# InstrumentationBoard.net
KiCad netlist of a schematic drawn in EAGLE
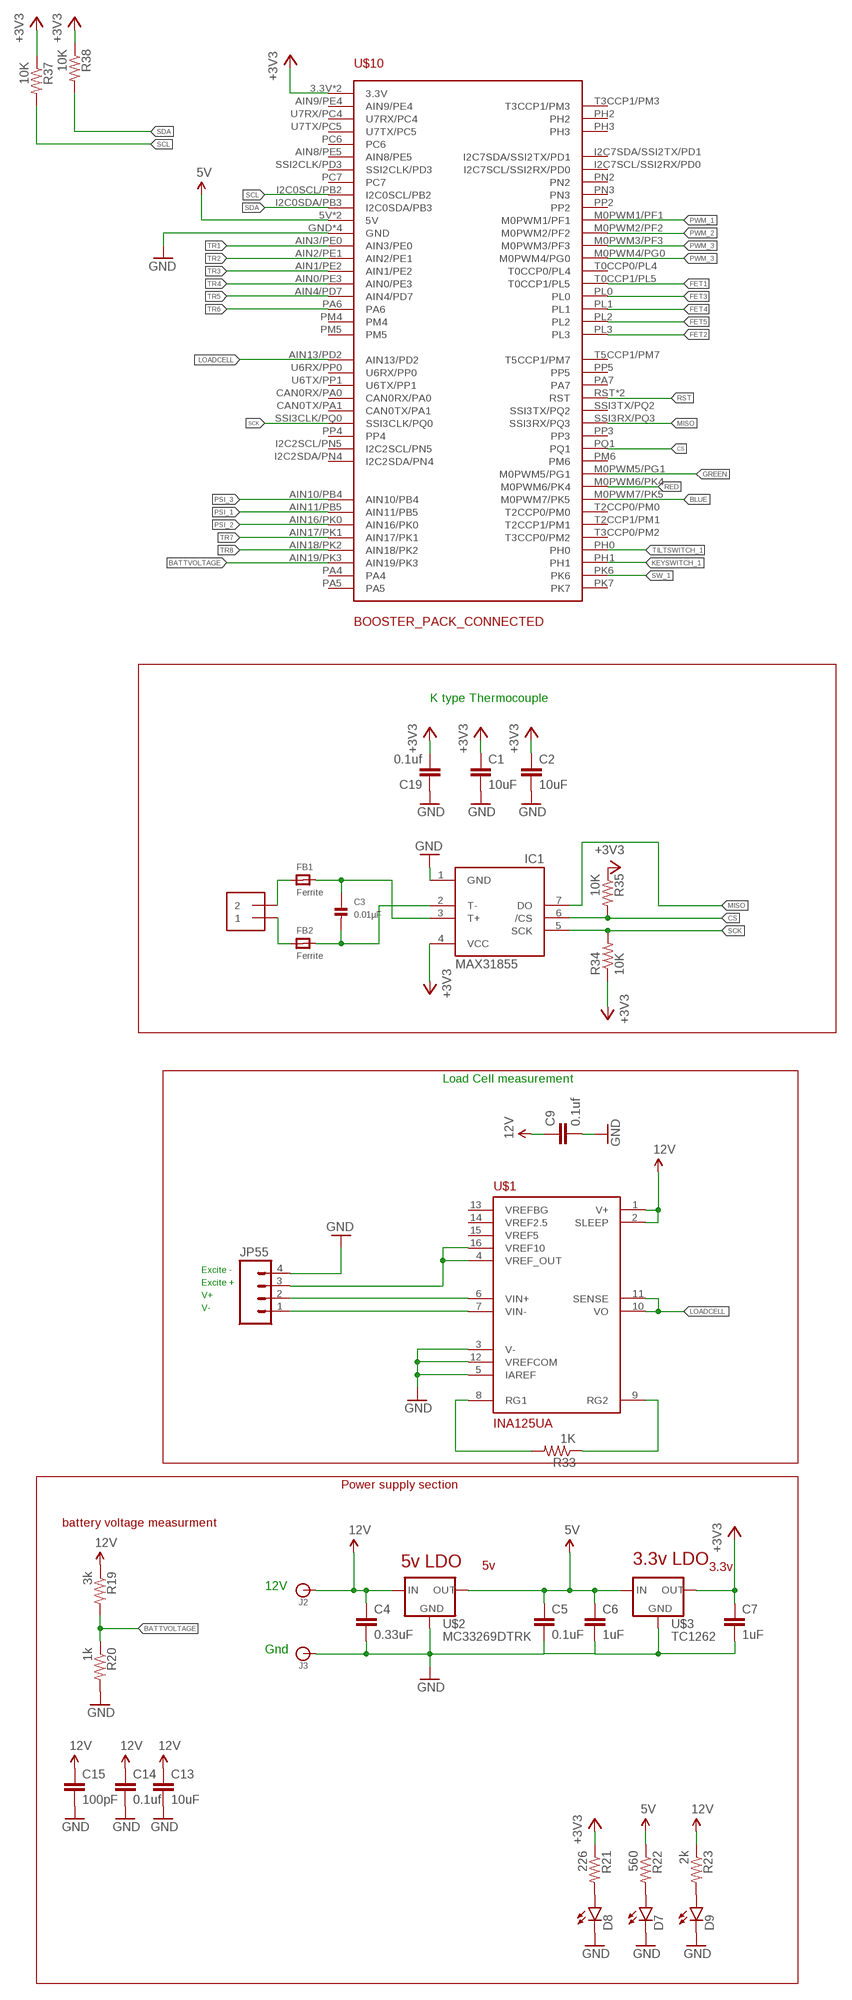
[diagram p0: schematic, sheet 1, part 1 of 2]
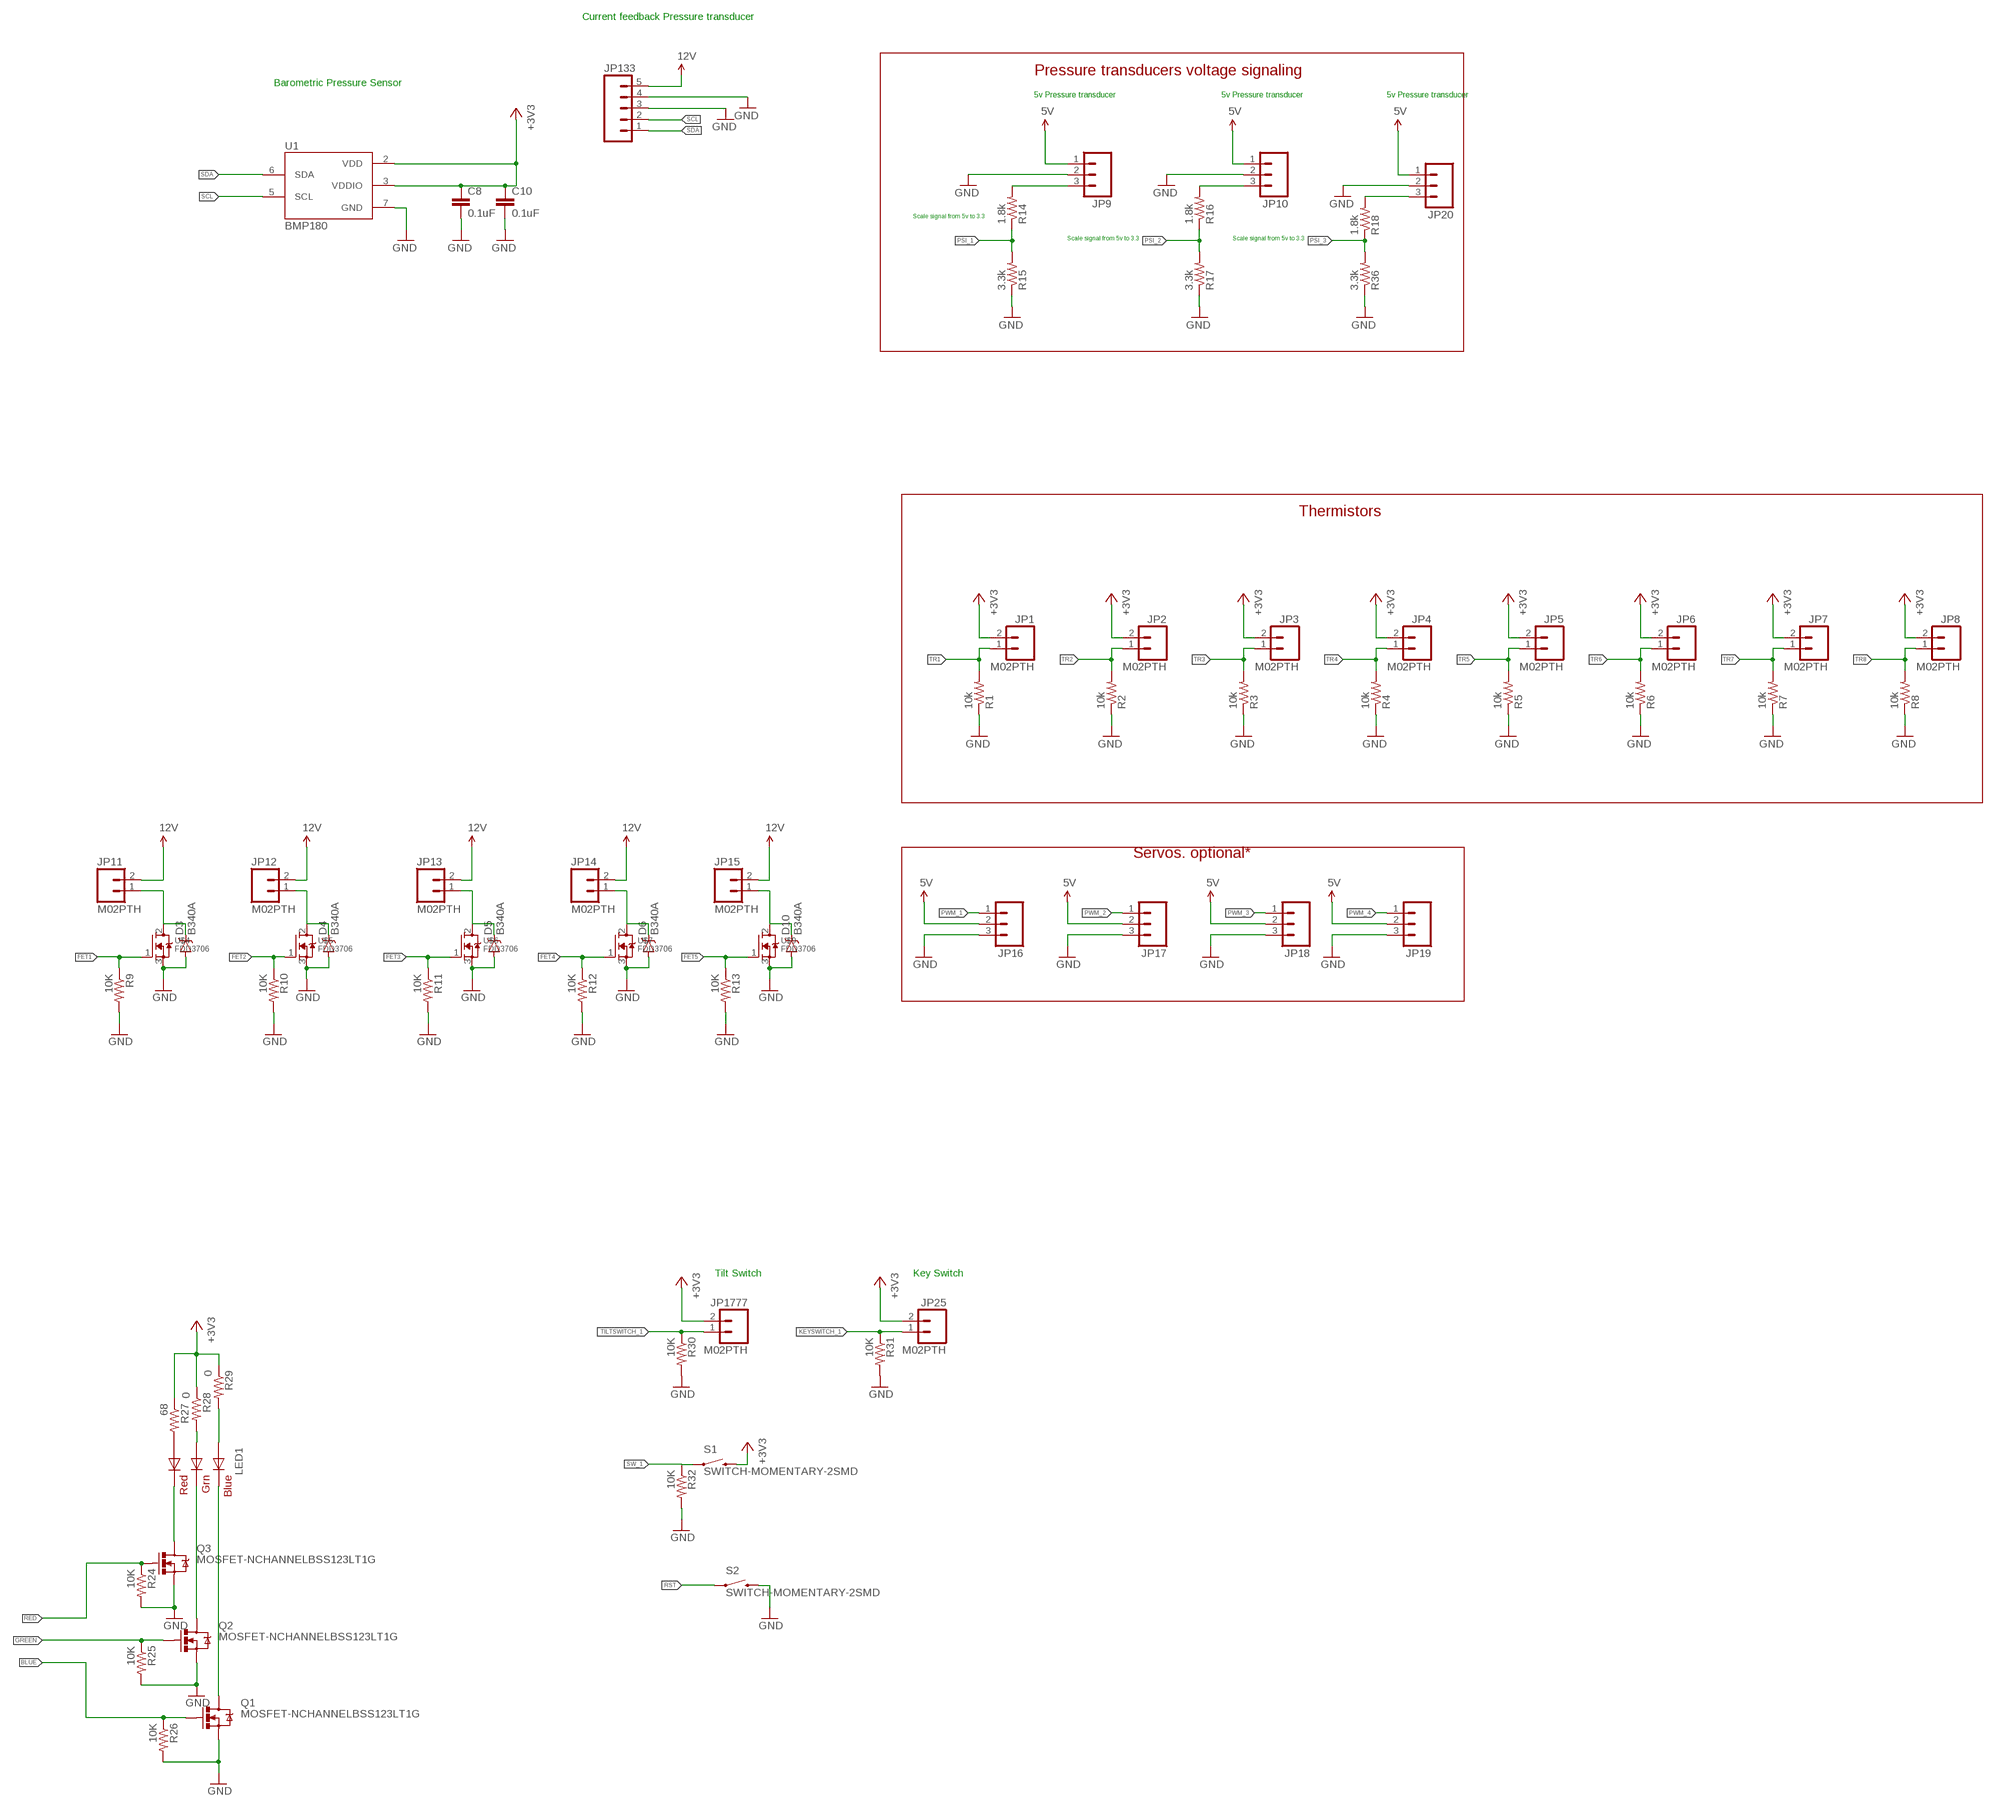
[diagram p1: schematic, sheet 1, part 2 of 2]

(export (version "E")
  (design (tool "Eeschema 10.0.6"))
  (components
    (comp (ref "C1")
      (value "10uF")
      (footprint "eagle-import:0805")
      (libsource (lib "eagle-import") (part "CAP0805"))
    )
    (comp (ref "C2")
      (value "10uF")
      (footprint "eagle-import:0805")
      (libsource (lib "eagle-import") (part "CAP0805"))
    )
    (comp (ref "C3")
      (value "0.01µF")
      (footprint "eagle-import:_0805")
      (libsource (lib "eagle-import") (part "CAP_CERAMIC_0805"))
    )
    (comp (ref "C4")
      (value "0.33uF")
      (footprint "eagle-import:0805")
      (libsource (lib "eagle-import") (part "CAP0805"))
    )
    (comp (ref "C5")
      (value "0.1uF")
      (footprint "eagle-import:0805")
      (libsource (lib "eagle-import") (part "CAP0805"))
    )
    (comp (ref "C6")
      (value "1uF")
      (footprint "eagle-import:0805")
      (libsource (lib "eagle-import") (part "CAP0805"))
    )
    (comp (ref "C7")
      (value "1uF")
      (footprint "eagle-import:0805")
      (libsource (lib "eagle-import") (part "CAP0805"))
    )
    (comp (ref "C8")
      (value "0.1uF")
      (footprint "eagle-import:0805")
      (libsource (lib "eagle-import") (part "CAP0805"))
    )
    (comp (ref "C9")
      (value "0.1uf")
      (footprint "eagle-import:0805")
      (libsource (lib "eagle-import") (part "CAP0805"))
    )
    (comp (ref "C10")
      (value "0.1uF")
      (footprint "eagle-import:0805")
      (libsource (lib "eagle-import") (part "CAP0805"))
    )
    (comp (ref "C13")
      (value "10uF")
      (footprint "eagle-import:0805")
      (libsource (lib "eagle-import") (part "CAP0805"))
    )
    (comp (ref "C14")
      (value "0.1uf")
      (footprint "eagle-import:0805")
      (libsource (lib "eagle-import") (part "CAP0805"))
    )
    (comp (ref "C15")
      (value "100pF")
      (footprint "eagle-import:0805")
      (libsource (lib "eagle-import") (part "CAP0805"))
    )
    (comp (ref "C19")
      (value "0.1uf")
      (footprint "eagle-import:0805")
      (libsource (lib "eagle-import") (part "CAP0805"))
    )
    (comp (ref "D3")
      (value "B340A")
      (footprint "eagle-import:SMA-DIODE")
      (libsource (lib "eagle-import") (part "DIODE-SCHOTTKY-B340A"))
    )
    (comp (ref "D4")
      (value "B340A")
      (footprint "eagle-import:SMA-DIODE")
      (libsource (lib "eagle-import") (part "DIODE-SCHOTTKY-B340A"))
    )
    (comp (ref "D5")
      (value "B340A")
      (footprint "eagle-import:SMA-DIODE")
      (libsource (lib "eagle-import") (part "DIODE-SCHOTTKY-B340A"))
    )
    (comp (ref "D6")
      (value "B340A")
      (footprint "eagle-import:SMA-DIODE")
      (libsource (lib "eagle-import") (part "DIODE-SCHOTTKY-B340A"))
    )
    (comp (ref "D7")
      (value "LED1206")
      (footprint "eagle-import:LED-1206")
      (libsource (lib "eagle-import") (part "LED1206"))
    )
    (comp (ref "D8")
      (value "LED1206")
      (footprint "eagle-import:LED-1206")
      (libsource (lib "eagle-import") (part "LED1206"))
    )
    (comp (ref "D9")
      (value "LED1206")
      (footprint "eagle-import:LED-1206")
      (libsource (lib "eagle-import") (part "LED1206"))
    )
    (comp (ref "D10")
      (value "B340A")
      (footprint "eagle-import:SMA-DIODE")
      (libsource (lib "eagle-import") (part "DIODE-SCHOTTKY-B340A"))
    )
    (comp (ref "FB1")
      (value "Ferrite")
      (footprint "eagle-import:_0805")
      (libsource (lib "eagle-import") (part "FERRITE_0805"))
    )
    (comp (ref "FB2")
      (value "Ferrite")
      (footprint "eagle-import:_0805")
      (libsource (lib "eagle-import") (part "FERRITE_0805"))
    )
    (comp (ref "IC1")
      (value "MAX31855")
      (footprint "eagle-import:SO08")
      (libsource (lib "eagle-import") (part "MAX6675"))
    )
    (comp (ref "J1")
      (value "1X2-3.5MM")
      (footprint "eagle-import:1X2-3.5MM")
      (libsource (lib "eagle-import") (part "1X2-3.5MM"))
    )
    (comp (ref "J2")
      (value "BANANA_CONN")
      (footprint "eagle-import:BANANA_CONN")
      (libsource (lib "eagle-import") (part "BANANA_CONN"))
    )
    (comp (ref "J3")
      (value "BANANA_CONN")
      (footprint "eagle-import:BANANA_CONN")
      (libsource (lib "eagle-import") (part "BANANA_CONN"))
    )
    (comp (ref "JP1")
      (value "M02PTH")
      (footprint "eagle-import:1X02")
      (libsource (lib "eagle-import") (part "M02PTH"))
    )
    (comp (ref "JP2")
      (value "M02PTH")
      (footprint "eagle-import:1X02")
      (libsource (lib "eagle-import") (part "M02PTH"))
    )
    (comp (ref "JP3")
      (value "M02PTH")
      (footprint "eagle-import:1X02")
      (libsource (lib "eagle-import") (part "M02PTH"))
    )
    (comp (ref "JP4")
      (value "M02PTH")
      (footprint "eagle-import:1X02")
      (libsource (lib "eagle-import") (part "M02PTH"))
    )
    (comp (ref "JP5")
      (value "M02PTH")
      (footprint "eagle-import:1X02")
      (libsource (lib "eagle-import") (part "M02PTH"))
    )
    (comp (ref "JP6")
      (value "M02PTH")
      (footprint "eagle-import:1X02")
      (libsource (lib "eagle-import") (part "M02PTH"))
    )
    (comp (ref "JP7")
      (value "M02PTH")
      (footprint "eagle-import:1X02")
      (libsource (lib "eagle-import") (part "M02PTH"))
    )
    (comp (ref "JP8")
      (value "M02PTH")
      (footprint "eagle-import:1X02")
      (libsource (lib "eagle-import") (part "M02PTH"))
    )
    (comp (ref "JP9")
      (value "M03PTH")
      (footprint "eagle-import:1X03")
      (libsource (lib "eagle-import") (part "M03PTH"))
    )
    (comp (ref "JP10")
      (value "M03PTH")
      (footprint "eagle-import:1X03")
      (libsource (lib "eagle-import") (part "M03PTH"))
    )
    (comp (ref "JP11")
      (value "M02PTH")
      (footprint "eagle-import:1X02")
      (libsource (lib "eagle-import") (part "M02PTH"))
    )
    (comp (ref "JP12")
      (value "M02PTH")
      (footprint "eagle-import:1X02")
      (libsource (lib "eagle-import") (part "M02PTH"))
    )
    (comp (ref "JP13")
      (value "M02PTH")
      (footprint "eagle-import:1X02")
      (libsource (lib "eagle-import") (part "M02PTH"))
    )
    (comp (ref "JP14")
      (value "M02PTH")
      (footprint "eagle-import:1X02")
      (libsource (lib "eagle-import") (part "M02PTH"))
    )
    (comp (ref "JP15")
      (value "M02PTH")
      (footprint "eagle-import:1X02")
      (libsource (lib "eagle-import") (part "M02PTH"))
    )
    (comp (ref "JP16")
      (value "M03PTH")
      (footprint "eagle-import:1X03")
      (libsource (lib "eagle-import") (part "M03PTH"))
    )
    (comp (ref "JP17")
      (value "M03PTH")
      (footprint "eagle-import:1X03")
      (libsource (lib "eagle-import") (part "M03PTH"))
    )
    (comp (ref "JP18")
      (value "M03PTH")
      (footprint "eagle-import:1X03")
      (libsource (lib "eagle-import") (part "M03PTH"))
    )
    (comp (ref "JP19")
      (value "M03PTH")
      (footprint "eagle-import:1X03")
      (libsource (lib "eagle-import") (part "M03PTH"))
    )
    (comp (ref "JP20")
      (value "M03PTH")
      (footprint "eagle-import:1X03")
      (libsource (lib "eagle-import") (part "M03PTH"))
    )
    (comp (ref "JP25")
      (value "M02PTH")
      (footprint "eagle-import:1X02")
      (libsource (lib "eagle-import") (part "M02PTH"))
    )
    (comp (ref "JP55")
      (value "M04PTH")
      (footprint "eagle-import:1X04")
      (libsource (lib "eagle-import") (part "M04PTH"))
    )
    (comp (ref "JP133")
      (value "M05PTH")
      (footprint "eagle-import:1X05")
      (libsource (lib "eagle-import") (part "M05PTH"))
    )
    (comp (ref "JP1777")
      (value "M02PTH")
      (footprint "eagle-import:1X02")
      (libsource (lib "eagle-import") (part "M02PTH"))
    )
    (comp (ref "LED1")
      (value "RGBLED5050")
      (footprint "eagle-import:RGBLED5050")
      (libsource (lib "eagle-import") (part "RGBLED5050"))
    )
    (comp (ref "Q1")
      (value "MOSFET-NCHANNELBSS123LT1G")
      (footprint "eagle-import:SOT23-3")
      (libsource (lib "eagle-import") (part "MOSFET-NCHANNELBSS123LT1G"))
    )
    (comp (ref "Q2")
      (value "MOSFET-NCHANNELBSS123LT1G")
      (footprint "eagle-import:SOT23-3")
      (libsource (lib "eagle-import") (part "MOSFET-NCHANNELBSS123LT1G"))
    )
    (comp (ref "Q3")
      (value "MOSFET-NCHANNELBSS123LT1G")
      (footprint "eagle-import:SOT23-3")
      (libsource (lib "eagle-import") (part "MOSFET-NCHANNELBSS123LT1G"))
    )
    (comp (ref "R1")
      (value "10k")
      (footprint "eagle-import:0805")
      (libsource (lib "eagle-import") (part "RESISTOR0805-RES"))
    )
    (comp (ref "R2")
      (value "10k")
      (footprint "eagle-import:0805")
      (libsource (lib "eagle-import") (part "RESISTOR0805-RES"))
    )
    (comp (ref "R3")
      (value "10k")
      (footprint "eagle-import:0805")
      (libsource (lib "eagle-import") (part "RESISTOR0805-RES"))
    )
    (comp (ref "R4")
      (value "10k")
      (footprint "eagle-import:0805")
      (libsource (lib "eagle-import") (part "RESISTOR0805-RES"))
    )
    (comp (ref "R5")
      (value "10k")
      (footprint "eagle-import:0805")
      (libsource (lib "eagle-import") (part "RESISTOR0805-RES"))
    )
    (comp (ref "R6")
      (value "10k")
      (footprint "eagle-import:0805")
      (libsource (lib "eagle-import") (part "RESISTOR0805-RES"))
    )
    (comp (ref "R7")
      (value "10k")
      (footprint "eagle-import:0805")
      (libsource (lib "eagle-import") (part "RESISTOR0805-RES"))
    )
    (comp (ref "R8")
      (value "10k")
      (footprint "eagle-import:0805")
      (libsource (lib "eagle-import") (part "RESISTOR0805-RES"))
    )
    (comp (ref "R9")
      (value "10K")
      (footprint "eagle-import:0805")
      (libsource (lib "eagle-import") (part "RESISTOR0805-RES"))
    )
    (comp (ref "R10")
      (value "10K")
      (footprint "eagle-import:0805")
      (libsource (lib "eagle-import") (part "RESISTOR0805-RES"))
    )
    (comp (ref "R11")
      (value "10K")
      (footprint "eagle-import:0805")
      (libsource (lib "eagle-import") (part "RESISTOR0805-RES"))
    )
    (comp (ref "R12")
      (value "10K")
      (footprint "eagle-import:0805")
      (libsource (lib "eagle-import") (part "RESISTOR0805-RES"))
    )
    (comp (ref "R13")
      (value "10K")
      (footprint "eagle-import:0805")
      (libsource (lib "eagle-import") (part "RESISTOR0805-RES"))
    )
    (comp (ref "R14")
      (value "1.8k")
      (footprint "eagle-import:0805")
      (libsource (lib "eagle-import") (part "RESISTOR0805-RES"))
    )
    (comp (ref "R15")
      (value "3.3k")
      (footprint "eagle-import:0805")
      (libsource (lib "eagle-import") (part "RESISTOR0805-RES"))
    )
    (comp (ref "R16")
      (value "1.8k")
      (footprint "eagle-import:0805")
      (libsource (lib "eagle-import") (part "RESISTOR0805-RES"))
    )
    (comp (ref "R17")
      (value "3.3k")
      (footprint "eagle-import:0805")
      (libsource (lib "eagle-import") (part "RESISTOR0805-RES"))
    )
    (comp (ref "R18")
      (value "1.8k")
      (footprint "eagle-import:0805")
      (libsource (lib "eagle-import") (part "RESISTOR0805-RES"))
    )
    (comp (ref "R19")
      (value "3k")
      (footprint "eagle-import:0805")
      (libsource (lib "eagle-import") (part "RESISTOR0805-RES"))
    )
    (comp (ref "R20")
      (value "1k")
      (footprint "eagle-import:0805")
      (libsource (lib "eagle-import") (part "RESISTOR0805-RES"))
    )
    (comp (ref "R21")
      (value "226")
      (footprint "eagle-import:0805")
      (libsource (lib "eagle-import") (part "RESISTOR0805-RES"))
    )
    (comp (ref "R22")
      (value "560")
      (footprint "eagle-import:0805")
      (libsource (lib "eagle-import") (part "RESISTOR0805-RES"))
    )
    (comp (ref "R23")
      (value "2k")
      (footprint "eagle-import:0805")
      (libsource (lib "eagle-import") (part "RESISTOR0805-RES"))
    )
    (comp (ref "R24")
      (value "10K")
      (footprint "eagle-import:0805")
      (libsource (lib "eagle-import") (part "RESISTOR0805-RES"))
    )
    (comp (ref "R25")
      (value "10K")
      (footprint "eagle-import:0805")
      (libsource (lib "eagle-import") (part "RESISTOR0805-RES"))
    )
    (comp (ref "R26")
      (value "10K")
      (footprint "eagle-import:0805")
      (libsource (lib "eagle-import") (part "RESISTOR0805-RES"))
    )
    (comp (ref "R27")
      (value "68")
      (footprint "eagle-import:0805")
      (libsource (lib "eagle-import") (part "RESISTOR0805-RES"))
    )
    (comp (ref "R28")
      (value "0")
      (footprint "eagle-import:0805")
      (libsource (lib "eagle-import") (part "RESISTOR0805-RES"))
    )
    (comp (ref "R29")
      (value "0")
      (footprint "eagle-import:0805")
      (libsource (lib "eagle-import") (part "RESISTOR0805-RES"))
    )
    (comp (ref "R30")
      (value "10K")
      (footprint "eagle-import:0805")
      (libsource (lib "eagle-import") (part "RESISTOR0805-RES"))
    )
    (comp (ref "R31")
      (value "10K")
      (footprint "eagle-import:0805")
      (libsource (lib "eagle-import") (part "RESISTOR0805-RES"))
    )
    (comp (ref "R32")
      (value "10K")
      (footprint "eagle-import:0805")
      (libsource (lib "eagle-import") (part "RESISTOR0805-RES"))
    )
    (comp (ref "R33")
      (value "1K")
      (footprint "eagle-import:0805")
      (libsource (lib "eagle-import") (part "RESISTOR0805-RES"))
    )
    (comp (ref "R34")
      (value "10K")
      (footprint "eagle-import:0805")
      (libsource (lib "eagle-import") (part "RESISTOR0805-RES"))
    )
    (comp (ref "R35")
      (value "10K")
      (footprint "eagle-import:0805")
      (libsource (lib "eagle-import") (part "RESISTOR0805-RES"))
    )
    (comp (ref "R36")
      (value "3.3k")
      (footprint "eagle-import:0805")
      (libsource (lib "eagle-import") (part "RESISTOR0805-RES"))
    )
    (comp (ref "R37")
      (value "10K")
      (footprint "eagle-import:0805")
      (libsource (lib "eagle-import") (part "RESISTOR0805-RES"))
    )
    (comp (ref "R38")
      (value "10K")
      (footprint "eagle-import:0805")
      (libsource (lib "eagle-import") (part "RESISTOR0805-RES"))
    )
    (comp (ref "S1")
      (value "SWITCH-MOMENTARY-2SMD")
      (footprint "eagle-import:TACTILE-SWITCH-SMD")
      (libsource (lib "eagle-import") (part "SWITCH-MOMENTARY-2SMD"))
    )
    (comp (ref "S2")
      (value "SWITCH-MOMENTARY-2SMD")
      (footprint "eagle-import:TACTILE-SWITCH-SMD")
      (libsource (lib "eagle-import") (part "SWITCH-MOMENTARY-2SMD"))
    )
    (comp (ref "U$1")
      (value "INA125UA")
      (footprint "eagle-import:SO16")
      (fields (field (name "DIGIKEY_PART_NUMBER") "INA125UA-ND"))
      (libsource (lib "eagle-import") (part "INA125UA"))
    )
    (comp (ref "U$2")
      (value "MC33269DTRK")
      (footprint "eagle-import:TO-252")
      (libsource (lib "eagle-import") (part "MC33269DTRK"))
    )
    (comp (ref "U$3")
      (value "TC1262")
      (footprint "eagle-import:SOT223")
      (libsource (lib "eagle-import") (part "TC1262"))
    )
    (comp (ref "U$4")
      (value "FDD3706")
      (footprint "eagle-import:TO-252")
      (fields (field (name "DIGIKEY_PART_NUMBER") "FDD3706FSCT-ND"))
      (libsource (lib "eagle-import") (part "FDD3706"))
    )
    (comp (ref "U$5")
      (value "FDD3706")
      (footprint "eagle-import:TO-252")
      (fields (field (name "DIGIKEY_PART_NUMBER") "FDD3706FSCT-ND"))
      (libsource (lib "eagle-import") (part "FDD3706"))
    )
    (comp (ref "U$6")
      (value "FDD3706")
      (footprint "eagle-import:TO-252")
      (fields (field (name "DIGIKEY_PART_NUMBER") "FDD3706FSCT-ND"))
      (libsource (lib "eagle-import") (part "FDD3706"))
    )
    (comp (ref "U$7")
      (value "FDD3706")
      (footprint "eagle-import:TO-252")
      (fields (field (name "DIGIKEY_PART_NUMBER") "FDD3706FSCT-ND"))
      (libsource (lib "eagle-import") (part "FDD3706"))
    )
    (comp (ref "U$9")
      (value "FDD3706")
      (footprint "eagle-import:TO-252")
      (fields (field (name "DIGIKEY_PART_NUMBER") "FDD3706FSCT-ND"))
      (libsource (lib "eagle-import") (part "FDD3706"))
    )
    (comp (ref "U$10")
      (value "BOOSTER_PACK_CONNECTED")
      (footprint "eagle-import:TI_CONNECTED_BOOSTER")
      (libsource (lib "eagle-import") (part "BOOSTER_PACK_CONNECTED"))
    )
    (comp (ref "U1")
      (value "BMP180")
      (footprint "eagle-import:BMP180")
      (libsource (lib "eagle-import") (part "BMP180"))
    )
  )
  (nets
    (net (code "1") (name "+3V3") (class "Default")
      (node (ref "C1") (pin "1") (pinfunction "1_1") (pintype "passive"))
      (node (ref "C10") (pin "1") (pinfunction "1_1") (pintype "passive"))
      (node (ref "C19") (pin "2") (pinfunction "2_2") (pintype "passive"))
      (node (ref "C2") (pin "1") (pinfunction "1_1") (pintype "passive"))
      (node (ref "C7") (pin "1") (pinfunction "1_1") (pintype "passive"))
      (node (ref "C8") (pin "1") (pinfunction "1_1") (pintype "passive"))
      (node (ref "IC1") (pin "4") (pinfunction "VCC_4") (pintype "power_in"))
      (node (ref "JP1") (pin "2") (pinfunction "2_2") (pintype "passive"))
      (node (ref "JP1777") (pin "2") (pinfunction "2_2") (pintype "passive"))
      (node (ref "JP2") (pin "2") (pinfunction "2_2") (pintype "passive"))
      (node (ref "JP25") (pin "2") (pinfunction "2_2") (pintype "passive"))
      (node (ref "JP3") (pin "2") (pinfunction "2_2") (pintype "passive"))
      (node (ref "JP4") (pin "2") (pinfunction "2_2") (pintype "passive"))
      (node (ref "JP5") (pin "2") (pinfunction "2_2") (pintype "passive"))
      (node (ref "JP6") (pin "2") (pinfunction "2_2") (pintype "passive"))
      (node (ref "JP7") (pin "2") (pinfunction "2_2") (pintype "passive"))
      (node (ref "JP8") (pin "2") (pinfunction "2_2") (pintype "passive"))
      (node (ref "R21") (pin "1") (pinfunction "1_1") (pintype "passive"))
      (node (ref "R27") (pin "1") (pinfunction "1_1") (pintype "passive"))
      (node (ref "R28") (pin "1") (pinfunction "1_1") (pintype "passive"))
      (node (ref "R29") (pin "1") (pinfunction "1_1") (pintype "passive"))
      (node (ref "R34") (pin "1") (pinfunction "1_1") (pintype "passive"))
      (node (ref "R35") (pin "1") (pinfunction "1_1") (pintype "passive"))
      (node (ref "R37") (pin "1") (pinfunction "1_1") (pintype "passive"))
      (node (ref "R38") (pin "1") (pinfunction "1_1") (pintype "passive"))
      (node (ref "S1") (pin "3") (pinfunction "2_3") (pintype "passive"))
      (node (ref "U$10") (pin "3.3V") (pinfunction "3.3V_3.3V") (pintype "bidirectional"))
      (node (ref "U$10") (pin "3.3V1") (pinfunction "3.3V_3.3V1") (pintype "bidirectional"))
      (node (ref "U$3") (pin "3") (pinfunction "OUT_3") (pintype "output"))
      (node (ref "U1") (pin "2") (pinfunction "VDD_2") (pintype "power_in"))
      (node (ref "U1") (pin "3") (pinfunction "VDDIO_3") (pintype "power_in"))
    )
    (net (code "2") (name "5V") (class "Default")
      (node (ref "C5") (pin "1") (pinfunction "1_1") (pintype "passive"))
      (node (ref "C6") (pin "1") (pinfunction "1_1") (pintype "passive"))
      (node (ref "JP10") (pin "1") (pinfunction "1_1") (pintype "passive"))
      (node (ref "JP16") (pin "2") (pinfunction "2_2") (pintype "passive"))
      (node (ref "JP17") (pin "2") (pinfunction "2_2") (pintype "passive"))
      (node (ref "JP18") (pin "2") (pinfunction "2_2") (pintype "passive"))
      (node (ref "JP19") (pin "2") (pinfunction "2_2") (pintype "passive"))
      (node (ref "JP20") (pin "1") (pinfunction "1_1") (pintype "passive"))
      (node (ref "JP9") (pin "1") (pinfunction "1_1") (pintype "passive"))
      (node (ref "R22") (pin "1") (pinfunction "1_1") (pintype "passive"))
      (node (ref "U$10") (pin "5V") (pinfunction "5V_5V") (pintype "bidirectional"))
      (node (ref "U$10") (pin "5V1") (pinfunction "5V_5V1") (pintype "bidirectional"))
      (node (ref "U$2") (pin "2") (pinfunction "OUT_2") (pintype "output"))
      (node (ref "U$3") (pin "1") (pinfunction "IN_1") (pintype "input"))
    )
    (net (code "3") (name "12V") (class "Default")
      (node (ref "C13") (pin "1") (pinfunction "1_1") (pintype "passive"))
      (node (ref "C14") (pin "1") (pinfunction "1_1") (pintype "passive"))
      (node (ref "C15") (pin "1") (pinfunction "1_1") (pintype "passive"))
      (node (ref "C4") (pin "1") (pinfunction "1_1") (pintype "passive"))
      (node (ref "C9") (pin "1") (pinfunction "1_1") (pintype "passive"))
      (node (ref "J2") (pin "P$1") (pinfunction "1_P$1") (pintype "passive"))
      (node (ref "JP11") (pin "2") (pinfunction "2_2") (pintype "passive"))
      (node (ref "JP12") (pin "2") (pinfunction "2_2") (pintype "passive"))
      (node (ref "JP13") (pin "2") (pinfunction "2_2") (pintype "passive"))
      (node (ref "JP133") (pin "5") (pinfunction "5_5") (pintype "passive"))
      (node (ref "JP14") (pin "2") (pinfunction "2_2") (pintype "passive"))
      (node (ref "JP15") (pin "2") (pinfunction "2_2") (pintype "passive"))
      (node (ref "R19") (pin "1") (pinfunction "1_1") (pintype "passive"))
      (node (ref "R23") (pin "1") (pinfunction "1_1") (pintype "passive"))
      (node (ref "U$1") (pin "1") (pinfunction "V+_1") (pintype "bidirectional"))
      (node (ref "U$1") (pin "2") (pinfunction "SLEEP_2") (pintype "bidirectional"))
      (node (ref "U$2") (pin "3") (pinfunction "IN_3") (pintype "input"))
    )
    (net (code "4") (name "BATTVOLTAGE") (class "Default")
      (node (ref "R19") (pin "2") (pinfunction "2_2") (pintype "passive"))
      (node (ref "R20") (pin "1") (pinfunction "1_1") (pintype "passive"))
      (node (ref "U$10") (pin "AIN19/PK3") (pinfunction "AIN19/PK3_AIN19/PK3") (pintype "bidirectional"))
    )
    (net (code "5") (name "BLUE") (class "Default")
      (node (ref "Q1") (pin "1") (pinfunction "G_1") (pintype "passive"))
      (node (ref "R26") (pin "1") (pinfunction "1_1") (pintype "passive"))
      (node (ref "U$10") (pin "M0PWM7/PK5") (pinfunction "M0PWM7/PK5_M0PWM7/PK5") (pintype "bidirectional"))
    )
    (net (code "6") (name "CS") (class "Default")
      (node (ref "IC1") (pin "6") (pinfunction "/CS_6") (pintype "input"))
      (node (ref "R35") (pin "2") (pinfunction "2_2") (pintype "passive"))
      (node (ref "U$10") (pin "PQ1") (pinfunction "PQ1_PQ1") (pintype "bidirectional"))
    )
    (net (code "7") (name "FET1") (class "Default")
      (node (ref "R9") (pin "1") (pinfunction "1_1") (pintype "passive"))
      (node (ref "U$10") (pin "T0CCP1/PL5") (pinfunction "T0CCP1/PL5_T0CCP1/PL5") (pintype "bidirectional"))
      (node (ref "U$4") (pin "1") (pinfunction "G_1") (pintype "bidirectional"))
    )
    (net (code "8") (name "FET2") (class "Default")
      (node (ref "R10") (pin "1") (pinfunction "1_1") (pintype "passive"))
      (node (ref "U$10") (pin "PL3") (pinfunction "PL3_PL3") (pintype "bidirectional"))
      (node (ref "U$5") (pin "1") (pinfunction "G_1") (pintype "bidirectional"))
    )
    (net (code "9") (name "FET3") (class "Default")
      (node (ref "R11") (pin "1") (pinfunction "1_1") (pintype "passive"))
      (node (ref "U$10") (pin "PL0") (pinfunction "PL0_PL0") (pintype "bidirectional"))
      (node (ref "U$6") (pin "1") (pinfunction "G_1") (pintype "bidirectional"))
    )
    (net (code "10") (name "FET4") (class "Default")
      (node (ref "R12") (pin "1") (pinfunction "1_1") (pintype "passive"))
      (node (ref "U$10") (pin "PL1") (pinfunction "PL1_PL1") (pintype "bidirectional"))
      (node (ref "U$7") (pin "1") (pinfunction "G_1") (pintype "bidirectional"))
    )
    (net (code "11") (name "FET5") (class "Default")
      (node (ref "R13") (pin "1") (pinfunction "1_1") (pintype "passive"))
      (node (ref "U$10") (pin "PL2") (pinfunction "PL2_PL2") (pintype "bidirectional"))
      (node (ref "U$9") (pin "1") (pinfunction "G_1") (pintype "bidirectional"))
    )
    (net (code "12") (name "GND") (class "Default")
      (node (ref "C1") (pin "2") (pinfunction "2_2") (pintype "passive"))
      (node (ref "C10") (pin "2") (pinfunction "2_2") (pintype "passive"))
      (node (ref "C13") (pin "2") (pinfunction "2_2") (pintype "passive"))
      (node (ref "C14") (pin "2") (pinfunction "2_2") (pintype "passive"))
      (node (ref "C15") (pin "2") (pinfunction "2_2") (pintype "passive"))
      (node (ref "C19") (pin "1") (pinfunction "1_1") (pintype "passive"))
      (node (ref "C2") (pin "2") (pinfunction "2_2") (pintype "passive"))
      (node (ref "C4") (pin "2") (pinfunction "2_2") (pintype "passive"))
      (node (ref "C5") (pin "2") (pinfunction "2_2") (pintype "passive"))
      (node (ref "C6") (pin "2") (pinfunction "2_2") (pintype "passive"))
      (node (ref "C7") (pin "2") (pinfunction "2_2") (pintype "passive"))
      (node (ref "C8") (pin "2") (pinfunction "2_2") (pintype "passive"))
      (node (ref "C9") (pin "2") (pinfunction "2_2") (pintype "passive"))
      (node (ref "D10") (pin "A") (pinfunction "A_A") (pintype "passive"))
      (node (ref "D3") (pin "A") (pinfunction "A_A") (pintype "passive"))
      (node (ref "D4") (pin "A") (pinfunction "A_A") (pintype "passive"))
      (node (ref "D5") (pin "A") (pinfunction "A_A") (pintype "passive"))
      (node (ref "D6") (pin "A") (pinfunction "A_A") (pintype "passive"))
      (node (ref "D7") (pin "C") (pinfunction "C_C") (pintype "passive"))
      (node (ref "D8") (pin "C") (pinfunction "C_C") (pintype "passive"))
      (node (ref "D9") (pin "C") (pinfunction "C_C") (pintype "passive"))
      (node (ref "IC1") (pin "1") (pinfunction "GND_1") (pintype "power_in"))
      (node (ref "J3") (pin "P$1") (pinfunction "1_P$1") (pintype "passive"))
      (node (ref "JP10") (pin "2") (pinfunction "2_2") (pintype "passive"))
      (node (ref "JP133") (pin "3") (pinfunction "3_3") (pintype "passive"))
      (node (ref "JP133") (pin "4") (pinfunction "4_4") (pintype "passive"))
      (node (ref "JP16") (pin "3") (pinfunction "3_3") (pintype "passive"))
      (node (ref "JP17") (pin "3") (pinfunction "3_3") (pintype "passive"))
      (node (ref "JP18") (pin "3") (pinfunction "3_3") (pintype "passive"))
      (node (ref "JP19") (pin "3") (pinfunction "3_3") (pintype "passive"))
      (node (ref "JP20") (pin "2") (pinfunction "2_2") (pintype "passive"))
      (node (ref "JP55") (pin "4") (pinfunction "4_4") (pintype "passive"))
      (node (ref "JP9") (pin "2") (pinfunction "2_2") (pintype "passive"))
      (node (ref "Q1") (pin "2") (pinfunction "S_2") (pintype "passive"))
      (node (ref "Q2") (pin "2") (pinfunction "S_2") (pintype "passive"))
      (node (ref "Q3") (pin "2") (pinfunction "S_2") (pintype "passive"))
      (node (ref "R1") (pin "1") (pinfunction "1_1") (pintype "passive"))
      (node (ref "R10") (pin "2") (pinfunction "2_2") (pintype "passive"))
      (node (ref "R11") (pin "2") (pinfunction "2_2") (pintype "passive"))
      (node (ref "R12") (pin "2") (pinfunction "2_2") (pintype "passive"))
      (node (ref "R13") (pin "2") (pinfunction "2_2") (pintype "passive"))
      (node (ref "R15") (pin "1") (pinfunction "1_1") (pintype "passive"))
      (node (ref "R17") (pin "1") (pinfunction "1_1") (pintype "passive"))
      (node (ref "R2") (pin "1") (pinfunction "1_1") (pintype "passive"))
      (node (ref "R20") (pin "2") (pinfunction "2_2") (pintype "passive"))
      (node (ref "R24") (pin "2") (pinfunction "2_2") (pintype "passive"))
      (node (ref "R25") (pin "2") (pinfunction "2_2") (pintype "passive"))
      (node (ref "R26") (pin "2") (pinfunction "2_2") (pintype "passive"))
      (node (ref "R3") (pin "1") (pinfunction "1_1") (pintype "passive"))
      (node (ref "R30") (pin "2") (pinfunction "2_2") (pintype "passive"))
      (node (ref "R31") (pin "2") (pinfunction "2_2") (pintype "passive"))
      (node (ref "R32") (pin "2") (pinfunction "2_2") (pintype "passive"))
      (node (ref "R36") (pin "1") (pinfunction "1_1") (pintype "passive"))
      (node (ref "R4") (pin "1") (pinfunction "1_1") (pintype "passive"))
      (node (ref "R5") (pin "1") (pinfunction "1_1") (pintype "passive"))
      (node (ref "R6") (pin "1") (pinfunction "1_1") (pintype "passive"))
      (node (ref "R7") (pin "1") (pinfunction "1_1") (pintype "passive"))
      (node (ref "R8") (pin "1") (pinfunction "1_1") (pintype "passive"))
      (node (ref "R9") (pin "2") (pinfunction "2_2") (pintype "passive"))
      (node (ref "S2") (pin "3") (pinfunction "2_3") (pintype "passive"))
      (node (ref "U$1") (pin "12") (pinfunction "VREFCOM_12") (pintype "bidirectional"))
      (node (ref "U$1") (pin "3") (pinfunction "V-_3") (pintype "bidirectional"))
      (node (ref "U$1") (pin "5") (pinfunction "IAREF_5") (pintype "bidirectional"))
      (node (ref "U$10") (pin "GND") (pinfunction "GND_GND") (pintype "bidirectional"))
      (node (ref "U$10") (pin "GND1") (pinfunction "GND_GND1") (pintype "bidirectional"))
      (node (ref "U$10") (pin "GND2") (pinfunction "GND_GND2") (pintype "bidirectional"))
      (node (ref "U$10") (pin "GND3") (pinfunction "GND_GND3") (pintype "bidirectional"))
      (node (ref "U$2") (pin "1") (pinfunction "GND_1") (pintype "input"))
      (node (ref "U$3") (pin "2") (pinfunction "GND_2") (pintype "input"))
      (node (ref "U$4") (pin "3") (pinfunction "S_3") (pintype "bidirectional"))
      (node (ref "U$5") (pin "3") (pinfunction "S_3") (pintype "bidirectional"))
      (node (ref "U$6") (pin "3") (pinfunction "S_3") (pintype "bidirectional"))
      (node (ref "U$7") (pin "3") (pinfunction "S_3") (pintype "bidirectional"))
      (node (ref "U$9") (pin "3") (pinfunction "S_3") (pintype "bidirectional"))
      (node (ref "U1") (pin "7") (pinfunction "GND_7") (pintype "power_in"))
    )
    (net (code "13") (name "GREEN") (class "Default")
      (node (ref "Q2") (pin "1") (pinfunction "G_1") (pintype "passive"))
      (node (ref "R25") (pin "1") (pinfunction "1_1") (pintype "passive"))
      (node (ref "U$10") (pin "M0PWM5/PG1") (pinfunction "M0PWM5/PG1_M0PWM5/PG1") (pintype "bidirectional"))
    )
    (net (code "14") (name "KEYSWITCH_1") (class "Default")
      (node (ref "JP25") (pin "1") (pinfunction "1_1") (pintype "passive"))
      (node (ref "R31") (pin "1") (pinfunction "1_1") (pintype "passive"))
      (node (ref "U$10") (pin "PH1") (pinfunction "PH1_PH1") (pintype "bidirectional"))
    )
    (net (code "15") (name "LOADCELL") (class "Default")
      (node (ref "U$1") (pin "10") (pinfunction "VO_10") (pintype "bidirectional"))
      (node (ref "U$1") (pin "11") (pinfunction "SENSE_11") (pintype "bidirectional"))
      (node (ref "U$10") (pin "AIN13/PD2") (pinfunction "AIN13/PD2_AIN13/PD2") (pintype "bidirectional"))
    )
    (net (code "16") (name "MISO") (class "Default")
      (node (ref "IC1") (pin "7") (pinfunction "DO_7") (pintype "output"))
      (node (ref "U$10") (pin "SSI3RX/PQ3") (pinfunction "SSI3RX/PQ3_SSI3RX/PQ3") (pintype "bidirectional"))
    )
    (net (code "17") (name "Net-(C3-P$1)") (class "Default")
      (node (ref "C3") (pin "1") (pinfunction "P$1_1") (pintype "passive"))
      (node (ref "FB1") (pin "2") (pinfunction "P$2_2") (pintype "passive"))
      (node (ref "IC1") (pin "3") (pinfunction "T+_3") (pintype "input"))
    )
    (net (code "18") (name "Net-(C3-P$2)") (class "Default")
      (node (ref "C3") (pin "2") (pinfunction "P$2_2") (pintype "passive"))
      (node (ref "FB2") (pin "2") (pinfunction "P$2_2") (pintype "passive"))
      (node (ref "IC1") (pin "2") (pinfunction "T-_2") (pintype "input"))
    )
    (net (code "19") (name "Net-(D7-PadA)") (class "Default")
      (node (ref "D7") (pin "A") (pinfunction "A_A") (pintype "passive"))
      (node (ref "R22") (pin "2") (pinfunction "2_2") (pintype "passive"))
    )
    (net (code "20") (name "Net-(D8-PadA)") (class "Default")
      (node (ref "D8") (pin "A") (pinfunction "A_A") (pintype "passive"))
      (node (ref "R21") (pin "2") (pinfunction "2_2") (pintype "passive"))
    )
    (net (code "21") (name "Net-(D9-PadA)") (class "Default")
      (node (ref "D9") (pin "A") (pinfunction "A_A") (pintype "passive"))
      (node (ref "R23") (pin "2") (pinfunction "2_2") (pintype "passive"))
    )
    (net (code "22") (name "Net-(FB1-P$1)") (class "Default")
      (node (ref "FB1") (pin "1") (pinfunction "P$1_1") (pintype "passive"))
      (node (ref "J1") (pin "2") (pinfunction "2_2") (pintype "passive"))
    )
    (net (code "23") (name "Net-(FB2-P$1)") (class "Default")
      (node (ref "FB2") (pin "1") (pinfunction "P$1_1") (pintype "passive"))
      (node (ref "J1") (pin "1") (pinfunction "1_1") (pintype "passive"))
    )
    (net (code "24") (name "Net-(JP9-Pad3)") (class "Default")
      (node (ref "JP9") (pin "3") (pinfunction "3_3") (pintype "passive"))
      (node (ref "R14") (pin "2") (pinfunction "2_2") (pintype "passive"))
    )
    (net (code "25") (name "Net-(JP10-Pad3)") (class "Default")
      (node (ref "JP10") (pin "3") (pinfunction "3_3") (pintype "passive"))
      (node (ref "R16") (pin "2") (pinfunction "2_2") (pintype "passive"))
    )
    (net (code "26") (name "Net-(JP20-Pad3)") (class "Default")
      (node (ref "JP20") (pin "3") (pinfunction "3_3") (pintype "passive"))
      (node (ref "R18") (pin "2") (pinfunction "2_2") (pintype "passive"))
    )
    (net (code "27") (name "Net-(LED1-BLUE_A)") (class "Default")
      (node (ref "LED1") (pin "3") (pinfunction "BLUE_A_3") (pintype "bidirectional"))
      (node (ref "R29") (pin "2") (pinfunction "2_2") (pintype "passive"))
    )
    (net (code "28") (name "Net-(LED1-BLUE_C)") (class "Default")
      (node (ref "LED1") (pin "4") (pinfunction "BLUE_C_4") (pintype "bidirectional"))
      (node (ref "Q1") (pin "3") (pinfunction "D_3") (pintype "passive"))
    )
    (net (code "29") (name "Net-(LED1-GREEN_A)") (class "Default")
      (node (ref "LED1") (pin "1") (pinfunction "GREEN_A_1") (pintype "bidirectional"))
      (node (ref "R28") (pin "2") (pinfunction "2_2") (pintype "passive"))
    )
    (net (code "30") (name "Net-(LED1-GREEN_C)") (class "Default")
      (node (ref "LED1") (pin "6") (pinfunction "GREEN_C_6") (pintype "bidirectional"))
      (node (ref "Q2") (pin "3") (pinfunction "D_3") (pintype "passive"))
    )
    (net (code "31") (name "Net-(LED1-RED_A)") (class "Default")
      (node (ref "LED1") (pin "2") (pinfunction "RED_A_2") (pintype "bidirectional"))
      (node (ref "R27") (pin "2") (pinfunction "2_2") (pintype "passive"))
    )
    (net (code "32") (name "Net-(LED1-RED_C)") (class "Default")
      (node (ref "LED1") (pin "5") (pinfunction "RED_C_5") (pintype "bidirectional"))
      (node (ref "Q3") (pin "3") (pinfunction "D_3") (pintype "passive"))
    )
    (net (code "33") (name "Net-(U$1-RG1)") (class "Default")
      (node (ref "R33") (pin "2") (pinfunction "2_2") (pintype "passive"))
      (node (ref "U$1") (pin "8") (pinfunction "RG1_8") (pintype "bidirectional"))
    )
    (net (code "34") (name "Net-(U$1-RG2)") (class "Default")
      (node (ref "R33") (pin "1") (pinfunction "1_1") (pintype "passive"))
      (node (ref "U$1") (pin "9") (pinfunction "RG2_9") (pintype "bidirectional"))
    )
    (net (code "35") (name "Net-(U$1-VIN+)") (class "Default")
      (node (ref "JP55") (pin "2") (pinfunction "2_2") (pintype "passive"))
      (node (ref "U$1") (pin "6") (pinfunction "VIN+_6") (pintype "bidirectional"))
    )
    (net (code "36") (name "Net-(U$1-VIN-)") (class "Default")
      (node (ref "JP55") (pin "1") (pinfunction "1_1") (pintype "passive"))
      (node (ref "U$1") (pin "7") (pinfunction "VIN-_7") (pintype "bidirectional"))
    )
    (net (code "37") (name "Net-(U$1-VREF10)") (class "Default")
      (node (ref "JP55") (pin "3") (pinfunction "3_3") (pintype "passive"))
      (node (ref "U$1") (pin "16") (pinfunction "VREF10_16") (pintype "bidirectional"))
      (node (ref "U$1") (pin "4") (pinfunction "VREF_OUT_4") (pintype "bidirectional"))
    )
    (net (code "38") (name "Net-(U$4-D)") (class "Default")
      (node (ref "D3") (pin "C") (pinfunction "C_C") (pintype "passive"))
      (node (ref "JP11") (pin "1") (pinfunction "1_1") (pintype "passive"))
      (node (ref "U$4") (pin "2") (pinfunction "D_2") (pintype "bidirectional"))
    )
    (net (code "39") (name "Net-(U$5-D)") (class "Default")
      (node (ref "D4") (pin "C") (pinfunction "C_C") (pintype "passive"))
      (node (ref "JP12") (pin "1") (pinfunction "1_1") (pintype "passive"))
      (node (ref "U$5") (pin "2") (pinfunction "D_2") (pintype "bidirectional"))
    )
    (net (code "40") (name "Net-(U$6-D)") (class "Default")
      (node (ref "D5") (pin "C") (pinfunction "C_C") (pintype "passive"))
      (node (ref "JP13") (pin "1") (pinfunction "1_1") (pintype "passive"))
      (node (ref "U$6") (pin "2") (pinfunction "D_2") (pintype "bidirectional"))
    )
    (net (code "41") (name "Net-(U$7-D)") (class "Default")
      (node (ref "D6") (pin "C") (pinfunction "C_C") (pintype "passive"))
      (node (ref "JP14") (pin "1") (pinfunction "1_1") (pintype "passive"))
      (node (ref "U$7") (pin "2") (pinfunction "D_2") (pintype "bidirectional"))
    )
    (net (code "42") (name "Net-(U$9-D)") (class "Default")
      (node (ref "D10") (pin "C") (pinfunction "C_C") (pintype "passive"))
      (node (ref "JP15") (pin "1") (pinfunction "1_1") (pintype "passive"))
      (node (ref "U$9") (pin "2") (pinfunction "D_2") (pintype "bidirectional"))
    )
    (net (code "43") (name "PSI_1") (class "Default")
      (node (ref "R14") (pin "1") (pinfunction "1_1") (pintype "passive"))
      (node (ref "R15") (pin "2") (pinfunction "2_2") (pintype "passive"))
      (node (ref "U$10") (pin "AIN11/PB5") (pinfunction "AIN11/PB5_AIN11/PB5") (pintype "bidirectional"))
    )
    (net (code "44") (name "PSI_2") (class "Default")
      (node (ref "R16") (pin "1") (pinfunction "1_1") (pintype "passive"))
      (node (ref "R17") (pin "2") (pinfunction "2_2") (pintype "passive"))
      (node (ref "U$10") (pin "AIN16/PK0") (pinfunction "AIN16/PK0_AIN16/PK0") (pintype "bidirectional"))
    )
    (net (code "45") (name "PSI_3") (class "Default")
      (node (ref "R18") (pin "1") (pinfunction "1_1") (pintype "passive"))
      (node (ref "R36") (pin "2") (pinfunction "2_2") (pintype "passive"))
      (node (ref "U$10") (pin "AIN10/PB4") (pinfunction "AIN10/PB4_AIN10/PB4") (pintype "bidirectional"))
    )
    (net (code "46") (name "PWM_1") (class "Default")
      (node (ref "JP16") (pin "1") (pinfunction "1_1") (pintype "passive"))
      (node (ref "U$10") (pin "M0PWM1/PF1") (pinfunction "M0PWM1/PF1_M0PWM1/PF1") (pintype "bidirectional"))
    )
    (net (code "47") (name "PWM_2") (class "Default")
      (node (ref "JP17") (pin "1") (pinfunction "1_1") (pintype "passive"))
      (node (ref "U$10") (pin "M0PWM2/PF2") (pinfunction "M0PWM2/PF2_M0PWM2/PF2") (pintype "bidirectional"))
    )
    (net (code "48") (name "PWM_3") (class "Default")
      (node (ref "JP18") (pin "1") (pinfunction "1_1") (pintype "passive"))
      (node (ref "U$10") (pin "M0PWM3/PF3") (pinfunction "M0PWM3/PF3_M0PWM3/PF3") (pintype "bidirectional"))
    )
    (net (code "49") (name "PWM_4") (class "Default")
      (node (ref "JP19") (pin "1") (pinfunction "1_1") (pintype "passive"))
      (node (ref "U$10") (pin "M0PWM4/PG0") (pinfunction "M0PWM4/PG0_M0PWM4/PG0") (pintype "bidirectional"))
    )
    (net (code "50") (name "RED") (class "Default")
      (node (ref "Q3") (pin "1") (pinfunction "G_1") (pintype "passive"))
      (node (ref "R24") (pin "1") (pinfunction "1_1") (pintype "passive"))
      (node (ref "U$10") (pin "M0PWM6/PK4") (pinfunction "M0PWM6/PK4_M0PWM6/PK4") (pintype "bidirectional"))
    )
    (net (code "51") (name "RST") (class "Default")
      (node (ref "S2") (pin "1") (pinfunction "1_1") (pintype "passive"))
      (node (ref "U$10") (pin "RST") (pinfunction "RST_RST") (pintype "bidirectional"))
      (node (ref "U$10") (pin "RST1") (pinfunction "RST_RST1") (pintype "bidirectional"))
    )
    (net (code "52") (name "SCK") (class "Default")
      (node (ref "IC1") (pin "5") (pinfunction "SCK_5") (pintype "input"))
      (node (ref "R34") (pin "2") (pinfunction "2_2") (pintype "passive"))
      (node (ref "U$10") (pin "SSI3CLK/PQ0") (pinfunction "SSI3CLK/PQ0_SSI3CLK/PQ0") (pintype "bidirectional"))
    )
    (net (code "53") (name "SCL") (class "Default")
      (node (ref "JP133") (pin "2") (pinfunction "2_2") (pintype "passive"))
      (node (ref "R37") (pin "2") (pinfunction "2_2") (pintype "passive"))
      (node (ref "U$10") (pin "I2C0SCL/PB2") (pinfunction "I2C0SCL/PB2_I2C0SCL/PB2") (pintype "bidirectional"))
      (node (ref "U1") (pin "5") (pinfunction "SCL_5") (pintype "input"))
    )
    (net (code "54") (name "SDA") (class "Default")
      (node (ref "JP133") (pin "1") (pinfunction "1_1") (pintype "passive"))
      (node (ref "R38") (pin "2") (pinfunction "2_2") (pintype "passive"))
      (node (ref "U$10") (pin "I2C0SDA/PB3") (pinfunction "I2C0SDA/PB3_I2C0SDA/PB3") (pintype "bidirectional"))
      (node (ref "U1") (pin "6") (pinfunction "SDA_6") (pintype "bidirectional"))
    )
    (net (code "55") (name "SW_1") (class "Default")
      (node (ref "R32") (pin "1") (pinfunction "1_1") (pintype "passive"))
      (node (ref "S1") (pin "1") (pinfunction "1_1") (pintype "passive"))
      (node (ref "U$10") (pin "PK6") (pinfunction "PK6_PK6") (pintype "bidirectional"))
    )
    (net (code "56") (name "TILTSWITCH_1") (class "Default")
      (node (ref "JP1777") (pin "1") (pinfunction "1_1") (pintype "passive"))
      (node (ref "R30") (pin "1") (pinfunction "1_1") (pintype "passive"))
      (node (ref "U$10") (pin "PH0") (pinfunction "PH0_PH0") (pintype "bidirectional"))
    )
    (net (code "57") (name "TR1") (class "Default")
      (node (ref "JP1") (pin "1") (pinfunction "1_1") (pintype "passive"))
      (node (ref "R1") (pin "2") (pinfunction "2_2") (pintype "passive"))
      (node (ref "U$10") (pin "AIN3/PE0") (pinfunction "AIN3/PE0_AIN3/PE0") (pintype "bidirectional"))
    )
    (net (code "58") (name "TR2") (class "Default")
      (node (ref "JP2") (pin "1") (pinfunction "1_1") (pintype "passive"))
      (node (ref "R2") (pin "2") (pinfunction "2_2") (pintype "passive"))
      (node (ref "U$10") (pin "AIN2/PE1") (pinfunction "AIN2/PE1_AIN2/PE1") (pintype "bidirectional"))
    )
    (net (code "59") (name "TR3") (class "Default")
      (node (ref "JP3") (pin "1") (pinfunction "1_1") (pintype "passive"))
      (node (ref "R3") (pin "2") (pinfunction "2_2") (pintype "passive"))
      (node (ref "U$10") (pin "AIN1/PE2") (pinfunction "AIN1/PE2_AIN1/PE2") (pintype "bidirectional"))
    )
    (net (code "60") (name "TR4") (class "Default")
      (node (ref "JP4") (pin "1") (pinfunction "1_1") (pintype "passive"))
      (node (ref "R4") (pin "2") (pinfunction "2_2") (pintype "passive"))
      (node (ref "U$10") (pin "AIN0/PE3") (pinfunction "AIN0/PE3_AIN0/PE3") (pintype "bidirectional"))
    )
    (net (code "61") (name "TR5") (class "Default")
      (node (ref "JP5") (pin "1") (pinfunction "1_1") (pintype "passive"))
      (node (ref "R5") (pin "2") (pinfunction "2_2") (pintype "passive"))
      (node (ref "U$10") (pin "AIN4/PD7") (pinfunction "AIN4/PD7_AIN4/PD7") (pintype "bidirectional"))
    )
    (net (code "62") (name "TR6") (class "Default")
      (node (ref "JP6") (pin "1") (pinfunction "1_1") (pintype "passive"))
      (node (ref "R6") (pin "2") (pinfunction "2_2") (pintype "passive"))
      (node (ref "U$10") (pin "PA6") (pinfunction "PA6_PA6") (pintype "bidirectional"))
    )
    (net (code "63") (name "TR7") (class "Default")
      (node (ref "JP7") (pin "1") (pinfunction "1_1") (pintype "passive"))
      (node (ref "R7") (pin "2") (pinfunction "2_2") (pintype "passive"))
      (node (ref "U$10") (pin "AIN17/PK1") (pinfunction "AIN17/PK1_AIN17/PK1") (pintype "bidirectional"))
    )
    (net (code "64") (name "TR8") (class "Default")
      (node (ref "JP8") (pin "1") (pinfunction "1_1") (pintype "passive"))
      (node (ref "R8") (pin "2") (pinfunction "2_2") (pintype "passive"))
      (node (ref "U$10") (pin "AIN18/PK2") (pinfunction "AIN18/PK2_AIN18/PK2") (pintype "bidirectional"))
    )
    (net (code "65") (name "unconnected-(U$1-VREF2.5-Pad14)") (class "Default")
      (node (ref "U$1") (pin "14") (pinfunction "VREF2.5_14") (pintype "bidirectional"))
    )
    (net (code "66") (name "unconnected-(U$1-VREF5-Pad15)") (class "Default")
      (node (ref "U$1") (pin "15") (pinfunction "VREF5_15") (pintype "bidirectional"))
    )
    (net (code "67") (name "unconnected-(U$1-VREFBG-Pad13)") (class "Default")
      (node (ref "U$1") (pin "13") (pinfunction "VREFBG_13") (pintype "bidirectional"))
    )
    (net (code "68") (name "unconnected-(U$10-PadAIN8{slash}PE5)") (class "Default")
      (node (ref "U$10") (pin "AIN8/PE5") (pinfunction "AIN8/PE5_AIN8/PE5") (pintype "bidirectional"))
    )
    (net (code "69") (name "unconnected-(U$10-PadAIN9{slash}PE4)") (class "Default")
      (node (ref "U$10") (pin "AIN9/PE4") (pinfunction "AIN9/PE4_AIN9/PE4") (pintype "bidirectional"))
    )
    (net (code "70") (name "unconnected-(U$10-PadCAN0RX{slash}PA0)") (class "Default")
      (node (ref "U$10") (pin "CAN0RX/PA0") (pinfunction "CAN0RX/PA0_CAN0RX/PA0") (pintype "bidirectional"))
    )
    (net (code "71") (name "unconnected-(U$10-PadCAN0TX{slash}PA1)") (class "Default")
      (node (ref "U$10") (pin "CAN0TX/PA1") (pinfunction "CAN0TX/PA1_CAN0TX/PA1") (pintype "bidirectional"))
    )
    (net (code "72") (name "unconnected-(U$10-PadI2C2SCL{slash}PN5)") (class "Default")
      (node (ref "U$10") (pin "I2C2SCL/PN5") (pinfunction "I2C2SCL/PN5_I2C2SCL/PN5") (pintype "bidirectional"))
    )
    (net (code "73") (name "unconnected-(U$10-PadI2C2SDA{slash}PN4)") (class "Default")
      (node (ref "U$10") (pin "I2C2SDA/PN4") (pinfunction "I2C2SDA/PN4_I2C2SDA/PN4") (pintype "bidirectional"))
    )
    (net (code "74") (name "unconnected-(U$10-PadI2C7SCL{slash}SSI2RX{slash}PD0)") (class "Default")
      (node (ref "U$10") (pin "I2C7SCL/SSI2RX/PD0") (pinfunction "I2C7SCL/SSI2RX/PD0_I2C7SCL/SSI2RX/PD0") (pintype "bidirectional"))
    )
    (net (code "75") (name "unconnected-(U$10-PadI2C7SDA{slash}SSI2TX{slash}PD1)") (class "Default")
      (node (ref "U$10") (pin "I2C7SDA/SSI2TX/PD1") (pinfunction "I2C7SDA/SSI2TX/PD1_I2C7SDA/SSI2TX/PD1") (pintype "bidirectional"))
    )
    (net (code "76") (name "unconnected-(U$10-PadPA4)") (class "Default")
      (node (ref "U$10") (pin "PA4") (pinfunction "PA4_PA4") (pintype "bidirectional"))
    )
    (net (code "77") (name "unconnected-(U$10-PadPA5)") (class "Default")
      (node (ref "U$10") (pin "PA5") (pinfunction "PA5_PA5") (pintype "bidirectional"))
    )
    (net (code "78") (name "unconnected-(U$10-PadPA7)") (class "Default")
      (node (ref "U$10") (pin "PA7") (pinfunction "PA7_PA7") (pintype "bidirectional"))
    )
    (net (code "79") (name "unconnected-(U$10-PadPC6)") (class "Default")
      (node (ref "U$10") (pin "PC6") (pinfunction "PC6_PC6") (pintype "bidirectional"))
    )
    (net (code "80") (name "unconnected-(U$10-PadPC7)") (class "Default")
      (node (ref "U$10") (pin "PC7") (pinfunction "PC7_PC7") (pintype "bidirectional"))
    )
    (net (code "81") (name "unconnected-(U$10-PadPH2)") (class "Default")
      (node (ref "U$10") (pin "PH2") (pinfunction "PH2_PH2") (pintype "bidirectional"))
    )
    (net (code "82") (name "unconnected-(U$10-PadPH3)") (class "Default")
      (node (ref "U$10") (pin "PH3") (pinfunction "PH3_PH3") (pintype "bidirectional"))
    )
    (net (code "83") (name "unconnected-(U$10-PadPK7)") (class "Default")
      (node (ref "U$10") (pin "PK7") (pinfunction "PK7_PK7") (pintype "bidirectional"))
    )
    (net (code "84") (name "unconnected-(U$10-PadPM4)") (class "Default")
      (node (ref "U$10") (pin "PM4") (pinfunction "PM4_PM4") (pintype "bidirectional"))
    )
    (net (code "85") (name "unconnected-(U$10-PadPM5)") (class "Default")
      (node (ref "U$10") (pin "PM5") (pinfunction "PM5_PM5") (pintype "bidirectional"))
    )
    (net (code "86") (name "unconnected-(U$10-PadPM6)") (class "Default")
      (node (ref "U$10") (pin "PM6") (pinfunction "PM6_PM6") (pintype "bidirectional"))
    )
    (net (code "87") (name "unconnected-(U$10-PadPN2)") (class "Default")
      (node (ref "U$10") (pin "PN2") (pinfunction "PN2_PN2") (pintype "bidirectional"))
    )
    (net (code "88") (name "unconnected-(U$10-PadPN3)") (class "Default")
      (node (ref "U$10") (pin "PN3") (pinfunction "PN3_PN3") (pintype "bidirectional"))
    )
    (net (code "89") (name "unconnected-(U$10-PadPP2)") (class "Default")
      (node (ref "U$10") (pin "PP2") (pinfunction "PP2_PP2") (pintype "bidirectional"))
    )
    (net (code "90") (name "unconnected-(U$10-PadPP3)") (class "Default")
      (node (ref "U$10") (pin "PP3") (pinfunction "PP3_PP3") (pintype "bidirectional"))
    )
    (net (code "91") (name "unconnected-(U$10-PadPP4)") (class "Default")
      (node (ref "U$10") (pin "PP4") (pinfunction "PP4_PP4") (pintype "bidirectional"))
    )
    (net (code "92") (name "unconnected-(U$10-PadPP5)") (class "Default")
      (node (ref "U$10") (pin "PP5") (pinfunction "PP5_PP5") (pintype "bidirectional"))
    )
    (net (code "93") (name "unconnected-(U$10-PadSSI2CLK{slash}PD3)") (class "Default")
      (node (ref "U$10") (pin "SSI2CLK/PD3") (pinfunction "SSI2CLK/PD3_SSI2CLK/PD3") (pintype "bidirectional"))
    )
    (net (code "94") (name "unconnected-(U$10-PadSSI3TX{slash}PQ2)") (class "Default")
      (node (ref "U$10") (pin "SSI3TX/PQ2") (pinfunction "SSI3TX/PQ2_SSI3TX/PQ2") (pintype "bidirectional"))
    )
    (net (code "95") (name "unconnected-(U$10-PadT0CCP0{slash}PL4)") (class "Default")
      (node (ref "U$10") (pin "T0CCP0/PL4") (pinfunction "T0CCP0/PL4_T0CCP0/PL4") (pintype "bidirectional"))
    )
    (net (code "96") (name "unconnected-(U$10-PadT2CCP0{slash}PM0)") (class "Default")
      (node (ref "U$10") (pin "T2CCP0/PM0") (pinfunction "T2CCP0/PM0_T2CCP0/PM0") (pintype "bidirectional"))
    )
    (net (code "97") (name "unconnected-(U$10-PadT2CCP1{slash}PM1)") (class "Default")
      (node (ref "U$10") (pin "T2CCP1/PM1") (pinfunction "T2CCP1/PM1_T2CCP1/PM1") (pintype "bidirectional"))
    )
    (net (code "98") (name "unconnected-(U$10-PadT3CCP0{slash}PM2)") (class "Default")
      (node (ref "U$10") (pin "T3CCP0/PM2") (pinfunction "T3CCP0/PM2_T3CCP0/PM2") (pintype "bidirectional"))
    )
    (net (code "99") (name "unconnected-(U$10-PadT3CCP1{slash}PM3)") (class "Default")
      (node (ref "U$10") (pin "T3CCP1/PM3") (pinfunction "T3CCP1/PM3_T3CCP1/PM3") (pintype "bidirectional"))
    )
    (net (code "100") (name "unconnected-(U$10-PadT5CCP1{slash}PM7)") (class "Default")
      (node (ref "U$10") (pin "T5CCP1/PM7") (pinfunction "T5CCP1/PM7_T5CCP1/PM7") (pintype "bidirectional"))
    )
    (net (code "101") (name "unconnected-(U$10-PadU6RX{slash}PP0)") (class "Default")
      (node (ref "U$10") (pin "U6RX/PP0") (pinfunction "U6RX/PP0_U6RX/PP0") (pintype "bidirectional"))
    )
    (net (code "102") (name "unconnected-(U$10-PadU6TX{slash}PP1)") (class "Default")
      (node (ref "U$10") (pin "U6TX/PP1") (pinfunction "U6TX/PP1_U6TX/PP1") (pintype "bidirectional"))
    )
    (net (code "103") (name "unconnected-(U$10-PadU7RX{slash}PC4)") (class "Default")
      (node (ref "U$10") (pin "U7RX/PC4") (pinfunction "U7RX/PC4_U7RX/PC4") (pintype "bidirectional"))
    )
    (net (code "104") (name "unconnected-(U$10-PadU7TX{slash}PC5)") (class "Default")
      (node (ref "U$10") (pin "U7TX/PC5") (pinfunction "U7TX/PC5_U7TX/PC5") (pintype "bidirectional"))
    )
  )
)
